# SD_CARD.net
KiCad netlist of a schematic drawn in Altium Designer
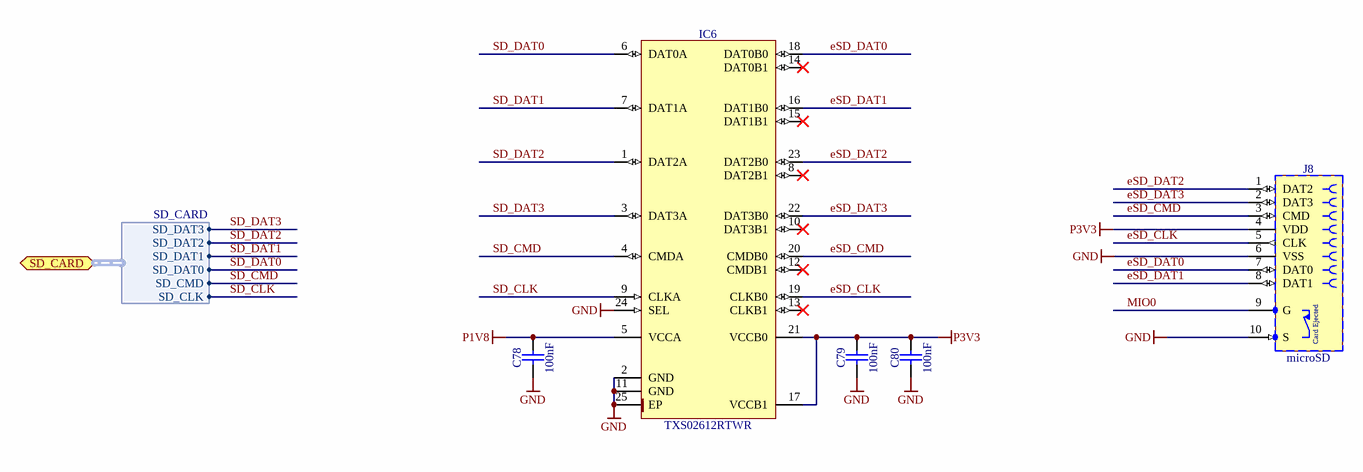
[diagram p0: SD_CARD.SchDoc]

(export (version "E")
  (design (tool "Eeschema 10.0.6"))
  (components
    (comp (ref "C78")
      (value "100nF")
      (footprint "CAPC1005X55N")
      (description "Non-polarised capacitor")
      (fields
        (field (name "PART NUMBER") "CC0402_100NF_16V_10%_X5R")
        (field (name "VOLTAGE") "16V")
        (field (name "AUTHOR") "CERN DEM JLC")
      )
      (libsource (lib "Capacitors") (part "Capacitor - non polarized"))
    )
    (comp (ref "C79")
      (value "100nF")
      (footprint "CAPC1005X55N")
      (description "Non-polarised capacitor")
      (fields
        (field (name "PART NUMBER") "CC0402_100NF_16V_10%_X5R")
        (field (name "VOLTAGE") "16V")
        (field (name "AUTHOR") "CERN DEM JLC")
      )
      (libsource (lib "Capacitors") (part "Capacitor - non polarized"))
    )
    (comp (ref "C80")
      (value "100nF")
      (footprint "CAPC1005X55N")
      (description "Non-polarised capacitor")
      (fields
        (field (name "PART NUMBER") "CC0402_100NF_16V_10%_X5R")
        (field (name "VOLTAGE") "16V")
        (field (name "AUTHOR") "CERN DEM JLC")
      )
      (libsource (lib "Capacitors") (part "Capacitor - non polarized"))
    )
    (comp (ref "IC6")
      (value "TXS02612RTWR")
      (footprint "QFN50P400X400X80-25N-S255")
      (description "SDIO Port Expander With Voltage-Level Translation")
      (fields (field (name "MANUFACTURER") "TEXAS INSTRUMENTS") (field (name "AUTHOR") "CERN DEM JLC"))
      (libsource (lib "ICs And Semiconductors") (part "TXS02612RTWR"))
    )
    (comp (ref "J8")
      (value "microSD")
      (footprint "ATTEND_112A-TAAR-R03")
      (description "Connector MicroSD 8 Pin + Switch")
      (fields
        (field (name "PART NUMBER") "ATTEND_112A-TAAR-R03")
        (field (name "MANUFACTURER") "ATTEND")
        (field (name "AUTHOR") "CERN DEM JMW")
      )
      (libsource (lib "Connectors") (part "Connector MicroSD 8 Pin + Switch"))
    )
  )
  (nets
    (net (code "2") (name "/MIO0") (class "Default")
      (node (ref "J8") (pin "9") (pinfunction "G_9") (pintype "power_in"))
    )
    (net (code "3") (name "/SD_CLK") (class "Default")
      (node (ref "IC6") (pin "9") (pinfunction "CLKA_9") (pintype "input"))
    )
    (net (code "4") (name "/SD_CMD") (class "Default")
      (node (ref "IC6") (pin "4") (pinfunction "CMDA_4") (pintype "bidirectional"))
    )
    (net (code "5") (name "/SD_DAT0") (class "Default")
      (node (ref "IC6") (pin "6") (pinfunction "DAT0A_6") (pintype "bidirectional"))
    )
    (net (code "6") (name "/SD_DAT1") (class "Default")
      (node (ref "IC6") (pin "7") (pinfunction "DAT1A_7") (pintype "bidirectional"))
    )
    (net (code "7") (name "/SD_DAT2") (class "Default")
      (node (ref "IC6") (pin "1") (pinfunction "DAT2A_1") (pintype "bidirectional"))
    )
    (net (code "8") (name "/SD_DAT3") (class "Default")
      (node (ref "IC6") (pin "3") (pinfunction "DAT3A_3") (pintype "bidirectional"))
    )
    (net (code "9") (name "/eSD_CLK") (class "Default")
      (node (ref "IC6") (pin "19") (pinfunction "CLKB0_19") (pintype "bidirectional"))
      (node (ref "J8") (pin "5") (pinfunction "CLK_5") (pintype "output"))
    )
    (net (code "10") (name "/eSD_CMD") (class "Default")
      (node (ref "IC6") (pin "20") (pinfunction "CMDB0_20") (pintype "bidirectional"))
      (node (ref "J8") (pin "3") (pinfunction "CMD_3") (pintype "bidirectional"))
    )
    (net (code "11") (name "/eSD_DAT0") (class "Default")
      (node (ref "IC6") (pin "18") (pinfunction "DAT0B0_18") (pintype "bidirectional"))
      (node (ref "J8") (pin "7") (pinfunction "DAT0_7") (pintype "bidirectional"))
    )
    (net (code "12") (name "/eSD_DAT1") (class "Default")
      (node (ref "IC6") (pin "16") (pinfunction "DAT1B0_16") (pintype "bidirectional"))
      (node (ref "J8") (pin "8") (pinfunction "DAT1_8") (pintype "bidirectional"))
    )
    (net (code "13") (name "/eSD_DAT2") (class "Default")
      (node (ref "IC6") (pin "23") (pinfunction "DAT2B0_23") (pintype "bidirectional"))
      (node (ref "J8") (pin "1") (pinfunction "DAT2_1") (pintype "bidirectional"))
    )
    (net (code "14") (name "/eSD_DAT3") (class "Default")
      (node (ref "IC6") (pin "22") (pinfunction "DAT3B0_22") (pintype "bidirectional"))
      (node (ref "J8") (pin "2") (pinfunction "DAT3_2") (pintype "bidirectional"))
    )
    (net (code "16") (name "GND") (class "Default")
      (node (ref "C78") (pin "1") (pinfunction "1_1") (pintype "passive"))
      (node (ref "C79") (pin "1") (pinfunction "1_1") (pintype "passive"))
      (node (ref "C80") (pin "1") (pinfunction "1_1") (pintype "passive"))
      (node (ref "IC6") (pin "11") (pinfunction "GND_11") (pintype "power_in"))
      (node (ref "IC6") (pin "2") (pinfunction "GND_2") (pintype "power_in"))
      (node (ref "IC6") (pin "24") (pinfunction "SEL_24") (pintype "input"))
      (node (ref "IC6") (pin "25") (pinfunction "EP_25") (pintype "power_in"))
      (node (ref "J8") (pin "10") (pinfunction "S_10") (pintype "input"))
      (node (ref "J8") (pin "6") (pinfunction "VSS_6") (pintype "power_in"))
    )
    (net (code "17") (name "P1V8") (class "Default")
      (node (ref "C78") (pin "2") (pinfunction "2_2") (pintype "passive"))
      (node (ref "IC6") (pin "5") (pinfunction "VCCA_5") (pintype "power_in"))
    )
    (net (code "18") (name "P3V3") (class "Default")
      (node (ref "C79") (pin "2") (pinfunction "2_2") (pintype "passive"))
      (node (ref "C80") (pin "2") (pinfunction "2_2") (pintype "passive"))
      (node (ref "IC6") (pin "17") (pinfunction "VCCB1_17") (pintype "power_in"))
      (node (ref "IC6") (pin "21") (pinfunction "VCCB0_21") (pintype "power_in"))
      (node (ref "J8") (pin "4") (pinfunction "VDD_4") (pintype "power_in"))
    )
    (net (code "19") (name "unconnected-(IC6-CLKB1-Pad13)") (class "Default")
      (node (ref "IC6") (pin "13") (pinfunction "CLKB1_13") (pintype "bidirectional+no_connect"))
    )
    (net (code "20") (name "unconnected-(IC6-CMDB1-Pad12)") (class "Default")
      (node (ref "IC6") (pin "12") (pinfunction "CMDB1_12") (pintype "bidirectional+no_connect"))
    )
    (net (code "21") (name "unconnected-(IC6-DAT0B1-Pad14)") (class "Default")
      (node (ref "IC6") (pin "14") (pinfunction "DAT0B1_14") (pintype "bidirectional+no_connect"))
    )
    (net (code "22") (name "unconnected-(IC6-DAT1B1-Pad15)") (class "Default")
      (node (ref "IC6") (pin "15") (pinfunction "DAT1B1_15") (pintype "bidirectional+no_connect"))
    )
    (net (code "23") (name "unconnected-(IC6-DAT2B1-Pad8)") (class "Default")
      (node (ref "IC6") (pin "8") (pinfunction "DAT2B1_8") (pintype "bidirectional+no_connect"))
    )
    (net (code "24") (name "unconnected-(IC6-DAT3B1-Pad10)") (class "Default")
      (node (ref "IC6") (pin "10") (pinfunction "DAT3B1_10") (pintype "bidirectional+no_connect"))
    )
  )
)
